# BRAKE_rev0.net
KiCad netlist of a schematic drawn in Altium Designer
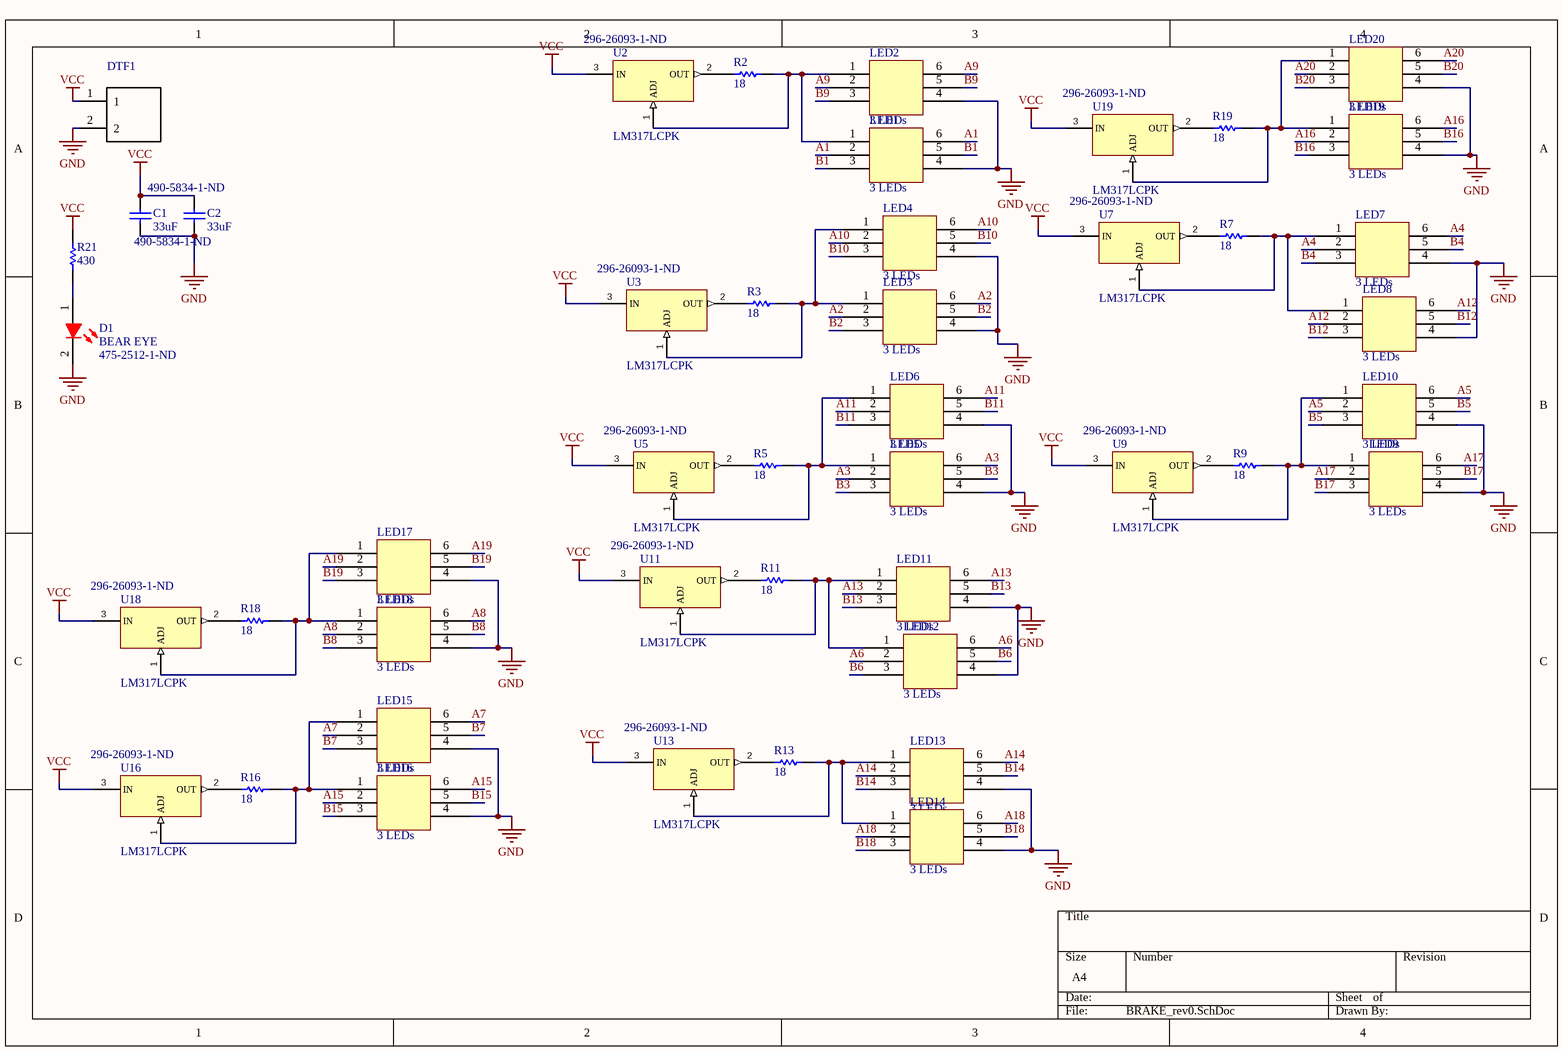
[diagram p0: BRAKE_rev0.SchDoc]

(export (version "E")
  (design (tool "Eeschema 10.0.6"))
  (components
    (comp (ref "C1")
      (value "33uF")
      (footprint "2J-Lead 6.1 x 5.3")
      (description "Capacitor (Semiconductor SIM Model)")
      (fields
        (field (name "SUPPLIER PART NUMBER 1") "490-5834-1-ND")
        (field (name "Comment") "Cap Semi")
        (field (name "PUBLISHER") "Altium Limited")
      )
      (libsource (lib "Miscellaneous Devices") (part "Cap Semi"))
    )
    (comp (ref "C2")
      (value "33uF")
      (footprint "2J-Lead 6.1 x 5.3")
      (description "Capacitor (Semiconductor SIM Model)")
      (fields
        (field (name "SUPPLIER PART NUMBER 1") "490-5834-1-ND")
        (field (name "Comment") "Cap Semi")
        (field (name "PUBLISHER") "Altium Limited")
      )
      (libsource (lib "Miscellaneous Devices") (part "Cap Semi"))
    )
    (comp (ref "D1")
      (value "BEAR EYE")
      (footprint "TOSH-0603LED_RED_V")
      (description "LED, Red 0603 (1608) 63mCd")
      (fields
        (field (name "MANUFACTURER") "Toshiba")
        (field (name "PARTNUMBER") "TLSU1008A(T04)")
        (field (name "SUPPLIER PART NUMBER 1") "475-2512-1-ND")
      )
      (libsource (lib "Altium Content Vault") (part "CMP-0444-00001-1"))
    )
    (comp (ref "DTF1")
      (value "DTF13-2P")
      (footprint "DTF13-2P")
      (description "DEUTSCH Automotive; DT RECP ASM")
      (fields (field (name "MF") "TE Connectivity") (field (name "DIGI-KEY_PART_NUMBER") "1734-1033-ND"))
      (libsource (lib "DTF13-2P") (part "DTF13-2P"))
    )
    (comp (ref "LED1")
      (value "3 LEDs")
      (footprint "3 channel led")
      (libsource (lib "PCB_BRAKE_LIGHT") (part "CLP6C-RKW-CYBA0AA3"))
    )
    (comp (ref "LED2")
      (value "3 LEDs")
      (footprint "3 channel led")
      (libsource (lib "PCB_BRAKE_LIGHT") (part "CLP6C-RKW-CYBA0AA3"))
    )
    (comp (ref "LED3")
      (value "3 LEDs")
      (footprint "3 channel led")
      (libsource (lib "PCB_BRAKE_LIGHT") (part "CLP6C-RKW-CYBA0AA3"))
    )
    (comp (ref "LED4")
      (value "3 LEDs")
      (footprint "3 channel led")
      (libsource (lib "PCB_BRAKE_LIGHT") (part "CLP6C-RKW-CYBA0AA3"))
    )
    (comp (ref "LED5")
      (value "3 LEDs")
      (footprint "3 channel led")
      (libsource (lib "PCB_BRAKE_LIGHT") (part "CLP6C-RKW-CYBA0AA3"))
    )
    (comp (ref "LED6")
      (value "3 LEDs")
      (footprint "3 channel led")
      (libsource (lib "PCB_BRAKE_LIGHT") (part "CLP6C-RKW-CYBA0AA3"))
    )
    (comp (ref "LED7")
      (value "3 LEDs")
      (footprint "3 channel led")
      (libsource (lib "PCB_BRAKE_LIGHT") (part "CLP6C-RKW-CYBA0AA3"))
    )
    (comp (ref "LED8")
      (value "3 LEDs")
      (footprint "3 channel led")
      (libsource (lib "PCB_BRAKE_LIGHT") (part "CLP6C-RKW-CYBA0AA3"))
    )
    (comp (ref "LED9")
      (value "3 LEDs")
      (footprint "3 channel led")
      (libsource (lib "PCB_BRAKE_LIGHT") (part "CLP6C-RKW-CYBA0AA3"))
    )
    (comp (ref "LED10")
      (value "3 LEDs")
      (footprint "3 channel led")
      (libsource (lib "PCB_BRAKE_LIGHT") (part "CLP6C-RKW-CYBA0AA3"))
    )
    (comp (ref "LED11")
      (value "3 LEDs")
      (footprint "3 channel led")
      (libsource (lib "PCB_BRAKE_LIGHT") (part "CLP6C-RKW-CYBA0AA3"))
    )
    (comp (ref "LED12")
      (value "3 LEDs")
      (footprint "3 channel led")
      (libsource (lib "PCB_BRAKE_LIGHT") (part "CLP6C-RKW-CYBA0AA3"))
    )
    (comp (ref "LED13")
      (value "3 LEDs")
      (footprint "3 channel led")
      (libsource (lib "PCB_BRAKE_LIGHT") (part "CLP6C-RKW-CYBA0AA3"))
    )
    (comp (ref "LED14")
      (value "3 LEDs")
      (footprint "3 channel led")
      (libsource (lib "PCB_BRAKE_LIGHT") (part "CLP6C-RKW-CYBA0AA3"))
    )
    (comp (ref "LED15")
      (value "3 LEDs")
      (footprint "3 channel led")
      (libsource (lib "PCB_BRAKE_LIGHT") (part "CLP6C-RKW-CYBA0AA3"))
    )
    (comp (ref "LED16")
      (value "3 LEDs")
      (footprint "3 channel led")
      (libsource (lib "PCB_BRAKE_LIGHT") (part "CLP6C-RKW-CYBA0AA3"))
    )
    (comp (ref "LED17")
      (value "3 LEDs")
      (footprint "3 channel led")
      (libsource (lib "PCB_BRAKE_LIGHT") (part "CLP6C-RKW-CYBA0AA3"))
    )
    (comp (ref "LED18")
      (value "3 LEDs")
      (footprint "3 channel led")
      (libsource (lib "PCB_BRAKE_LIGHT") (part "CLP6C-RKW-CYBA0AA3"))
    )
    (comp (ref "LED19")
      (value "3 LEDs")
      (footprint "3 channel led")
      (libsource (lib "PCB_BRAKE_LIGHT") (part "CLP6C-RKW-CYBA0AA3"))
    )
    (comp (ref "LED20")
      (value "3 LEDs")
      (footprint "3 channel led")
      (libsource (lib "PCB_BRAKE_LIGHT") (part "CLP6C-RKW-CYBA0AA3"))
    )
    (comp (ref "R2")
      (value "18")
      (footprint "RESC0603(1608)_L")
      (description "0603 (1608 Metric) Chip Resistor")
      (libsource (lib "Altium Content Vault") (part "RES_3"))
    )
    (comp (ref "R3")
      (value "18")
      (footprint "RESC0603(1608)_L")
      (description "0603 (1608 Metric) Chip Resistor")
      (libsource (lib "Altium Content Vault") (part "RES_3"))
    )
    (comp (ref "R5")
      (value "18")
      (footprint "RESC0603(1608)_L")
      (description "0603 (1608 Metric) Chip Resistor")
      (libsource (lib "Altium Content Vault") (part "RES_3"))
    )
    (comp (ref "R7")
      (value "18")
      (footprint "RESC0603(1608)_L")
      (description "0603 (1608 Metric) Chip Resistor")
      (libsource (lib "Altium Content Vault") (part "RES_3"))
    )
    (comp (ref "R9")
      (value "18")
      (footprint "RESC0603(1608)_L")
      (description "0603 (1608 Metric) Chip Resistor")
      (libsource (lib "Altium Content Vault") (part "RES_3"))
    )
    (comp (ref "R11")
      (value "18")
      (footprint "RESC0603(1608)_L")
      (description "0603 (1608 Metric) Chip Resistor")
      (libsource (lib "Altium Content Vault") (part "RES_3"))
    )
    (comp (ref "R13")
      (value "18")
      (footprint "RESC0603(1608)_L")
      (description "0603 (1608 Metric) Chip Resistor")
      (libsource (lib "Altium Content Vault") (part "RES_3"))
    )
    (comp (ref "R16")
      (value "18")
      (footprint "RESC0603(1608)_L")
      (description "0603 (1608 Metric) Chip Resistor")
      (libsource (lib "Altium Content Vault") (part "RES_3"))
    )
    (comp (ref "R18")
      (value "18")
      (footprint "RESC0603(1608)_L")
      (description "0603 (1608 Metric) Chip Resistor")
      (libsource (lib "Altium Content Vault") (part "RES_3"))
    )
    (comp (ref "R19")
      (value "18")
      (footprint "RESC0603(1608)_L")
      (description "0603 (1608 Metric) Chip Resistor")
      (libsource (lib "Altium Content Vault") (part "RES_3"))
    )
    (comp (ref "R21")
      (value "430")
      (footprint "RESC0603(1608)_L")
      (description "0603 (1608 Metric) Chip Resistor")
      (libsource (lib "Altium Content Vault") (part "RES_3"))
    )
    (comp (ref "U2")
      (value "LM317LCPK")
      (footprint "LM317LCPK")
      (fields (field (name "SUPPLIER PART NUMBER 1") "296-26093-1-ND"))
      (libsource (lib "BrakeLight_symbols") (part "LM317LCPK"))
    )
    (comp (ref "U3")
      (value "LM317LCPK")
      (footprint "LM317LCPK")
      (fields (field (name "SUPPLIER PART NUMBER 1") "296-26093-1-ND"))
      (libsource (lib "BrakeLight_symbols") (part "LM317LCPK"))
    )
    (comp (ref "U5")
      (value "LM317LCPK")
      (footprint "LM317LCPK")
      (fields (field (name "SUPPLIER PART NUMBER 1") "296-26093-1-ND"))
      (libsource (lib "BrakeLight_symbols") (part "LM317LCPK"))
    )
    (comp (ref "U7")
      (value "LM317LCPK")
      (footprint "LM317LCPK")
      (fields (field (name "SUPPLIER PART NUMBER 1") "296-26093-1-ND"))
      (libsource (lib "BrakeLight_symbols") (part "LM317LCPK"))
    )
    (comp (ref "U9")
      (value "LM317LCPK")
      (footprint "LM317LCPK")
      (fields (field (name "SUPPLIER PART NUMBER 1") "296-26093-1-ND"))
      (libsource (lib "BrakeLight_symbols") (part "LM317LCPK"))
    )
    (comp (ref "U11")
      (value "LM317LCPK")
      (footprint "LM317LCPK")
      (fields (field (name "SUPPLIER PART NUMBER 1") "296-26093-1-ND"))
      (libsource (lib "BrakeLight_symbols") (part "LM317LCPK"))
    )
    (comp (ref "U13")
      (value "LM317LCPK")
      (footprint "LM317LCPK")
      (fields (field (name "SUPPLIER PART NUMBER 1") "296-26093-1-ND"))
      (libsource (lib "BrakeLight_symbols") (part "LM317LCPK"))
    )
    (comp (ref "U16")
      (value "LM317LCPK")
      (footprint "LM317LCPK")
      (fields (field (name "SUPPLIER PART NUMBER 1") "296-26093-1-ND"))
      (libsource (lib "BrakeLight_symbols") (part "LM317LCPK"))
    )
    (comp (ref "U18")
      (value "LM317LCPK")
      (footprint "LM317LCPK")
      (fields (field (name "SUPPLIER PART NUMBER 1") "296-26093-1-ND"))
      (libsource (lib "BrakeLight_symbols") (part "LM317LCPK"))
    )
    (comp (ref "U19")
      (value "LM317LCPK")
      (footprint "LM317LCPK")
      (fields (field (name "SUPPLIER PART NUMBER 1") "296-26093-1-ND"))
      (libsource (lib "BrakeLight_symbols") (part "LM317LCPK"))
    )
  )
  (nets
    (net (code "1") (name "/A1") (class "Default")
      (node (ref "LED1") (pin "2") (pinfunction "2_2") (pintype "passive"))
      (node (ref "LED1") (pin "6") (pinfunction "6_6") (pintype "passive"))
    )
    (net (code "2") (name "/A2") (class "Default")
      (node (ref "LED3") (pin "2") (pinfunction "2_2") (pintype "passive"))
      (node (ref "LED3") (pin "6") (pinfunction "6_6") (pintype "passive"))
    )
    (net (code "3") (name "/A3") (class "Default")
      (node (ref "LED5") (pin "2") (pinfunction "2_2") (pintype "passive"))
      (node (ref "LED5") (pin "6") (pinfunction "6_6") (pintype "passive"))
    )
    (net (code "4") (name "/A4") (class "Default")
      (node (ref "LED7") (pin "2") (pinfunction "2_2") (pintype "passive"))
      (node (ref "LED7") (pin "6") (pinfunction "6_6") (pintype "passive"))
    )
    (net (code "5") (name "/A5") (class "Default")
      (node (ref "LED10") (pin "2") (pinfunction "2_2") (pintype "passive"))
      (node (ref "LED10") (pin "6") (pinfunction "6_6") (pintype "passive"))
    )
    (net (code "6") (name "/A6") (class "Default")
      (node (ref "LED12") (pin "2") (pinfunction "2_2") (pintype "passive"))
      (node (ref "LED12") (pin "6") (pinfunction "6_6") (pintype "passive"))
    )
    (net (code "7") (name "/A7") (class "Default")
      (node (ref "LED15") (pin "2") (pinfunction "2_2") (pintype "passive"))
      (node (ref "LED15") (pin "6") (pinfunction "6_6") (pintype "passive"))
    )
    (net (code "8") (name "/A8") (class "Default")
      (node (ref "LED18") (pin "2") (pinfunction "2_2") (pintype "passive"))
      (node (ref "LED18") (pin "6") (pinfunction "6_6") (pintype "passive"))
    )
    (net (code "9") (name "/A9") (class "Default")
      (node (ref "LED2") (pin "2") (pinfunction "2_2") (pintype "passive"))
      (node (ref "LED2") (pin "6") (pinfunction "6_6") (pintype "passive"))
    )
    (net (code "10") (name "/A10") (class "Default")
      (node (ref "LED4") (pin "2") (pinfunction "2_2") (pintype "passive"))
      (node (ref "LED4") (pin "6") (pinfunction "6_6") (pintype "passive"))
    )
    (net (code "11") (name "/A11") (class "Default")
      (node (ref "LED6") (pin "2") (pinfunction "2_2") (pintype "passive"))
      (node (ref "LED6") (pin "6") (pinfunction "6_6") (pintype "passive"))
    )
    (net (code "12") (name "/A12") (class "Default")
      (node (ref "LED8") (pin "2") (pinfunction "2_2") (pintype "passive"))
      (node (ref "LED8") (pin "6") (pinfunction "6_6") (pintype "passive"))
    )
    (net (code "13") (name "/A13") (class "Default")
      (node (ref "LED11") (pin "2") (pinfunction "2_2") (pintype "passive"))
      (node (ref "LED11") (pin "6") (pinfunction "6_6") (pintype "passive"))
    )
    (net (code "14") (name "/A14") (class "Default")
      (node (ref "LED13") (pin "2") (pinfunction "2_2") (pintype "passive"))
      (node (ref "LED13") (pin "6") (pinfunction "6_6") (pintype "passive"))
    )
    (net (code "15") (name "/A15") (class "Default")
      (node (ref "LED16") (pin "2") (pinfunction "2_2") (pintype "passive"))
      (node (ref "LED16") (pin "6") (pinfunction "6_6") (pintype "passive"))
    )
    (net (code "16") (name "/A16") (class "Default")
      (node (ref "LED19") (pin "2") (pinfunction "2_2") (pintype "passive"))
      (node (ref "LED19") (pin "6") (pinfunction "6_6") (pintype "passive"))
    )
    (net (code "17") (name "/A17") (class "Default")
      (node (ref "LED9") (pin "2") (pinfunction "2_2") (pintype "passive"))
      (node (ref "LED9") (pin "6") (pinfunction "6_6") (pintype "passive"))
    )
    (net (code "18") (name "/A18") (class "Default")
      (node (ref "LED14") (pin "2") (pinfunction "2_2") (pintype "passive"))
      (node (ref "LED14") (pin "6") (pinfunction "6_6") (pintype "passive"))
    )
    (net (code "19") (name "/A19") (class "Default")
      (node (ref "LED17") (pin "2") (pinfunction "2_2") (pintype "passive"))
      (node (ref "LED17") (pin "6") (pinfunction "6_6") (pintype "passive"))
    )
    (net (code "20") (name "/A20") (class "Default")
      (node (ref "LED20") (pin "2") (pinfunction "2_2") (pintype "passive"))
      (node (ref "LED20") (pin "6") (pinfunction "6_6") (pintype "passive"))
    )
    (net (code "21") (name "/B1") (class "Default")
      (node (ref "LED1") (pin "3") (pinfunction "3_3") (pintype "passive"))
      (node (ref "LED1") (pin "5") (pinfunction "5_5") (pintype "passive"))
    )
    (net (code "22") (name "/B2") (class "Default")
      (node (ref "LED3") (pin "3") (pinfunction "3_3") (pintype "passive"))
      (node (ref "LED3") (pin "5") (pinfunction "5_5") (pintype "passive"))
    )
    (net (code "23") (name "/B3") (class "Default")
      (node (ref "LED5") (pin "3") (pinfunction "3_3") (pintype "passive"))
      (node (ref "LED5") (pin "5") (pinfunction "5_5") (pintype "passive"))
    )
    (net (code "24") (name "/B4") (class "Default")
      (node (ref "LED7") (pin "3") (pinfunction "3_3") (pintype "passive"))
      (node (ref "LED7") (pin "5") (pinfunction "5_5") (pintype "passive"))
    )
    (net (code "25") (name "/B5") (class "Default")
      (node (ref "LED10") (pin "3") (pinfunction "3_3") (pintype "passive"))
      (node (ref "LED10") (pin "5") (pinfunction "5_5") (pintype "passive"))
    )
    (net (code "26") (name "/B6") (class "Default")
      (node (ref "LED12") (pin "3") (pinfunction "3_3") (pintype "passive"))
      (node (ref "LED12") (pin "5") (pinfunction "5_5") (pintype "passive"))
    )
    (net (code "27") (name "/B7") (class "Default")
      (node (ref "LED15") (pin "3") (pinfunction "3_3") (pintype "passive"))
      (node (ref "LED15") (pin "5") (pinfunction "5_5") (pintype "passive"))
    )
    (net (code "28") (name "/B8") (class "Default")
      (node (ref "LED18") (pin "3") (pinfunction "3_3") (pintype "passive"))
      (node (ref "LED18") (pin "5") (pinfunction "5_5") (pintype "passive"))
    )
    (net (code "29") (name "/B9") (class "Default")
      (node (ref "LED2") (pin "3") (pinfunction "3_3") (pintype "passive"))
      (node (ref "LED2") (pin "5") (pinfunction "5_5") (pintype "passive"))
    )
    (net (code "30") (name "/B10") (class "Default")
      (node (ref "LED4") (pin "3") (pinfunction "3_3") (pintype "passive"))
      (node (ref "LED4") (pin "5") (pinfunction "5_5") (pintype "passive"))
    )
    (net (code "31") (name "/B11") (class "Default")
      (node (ref "LED6") (pin "3") (pinfunction "3_3") (pintype "passive"))
      (node (ref "LED6") (pin "5") (pinfunction "5_5") (pintype "passive"))
    )
    (net (code "32") (name "/B12") (class "Default")
      (node (ref "LED8") (pin "3") (pinfunction "3_3") (pintype "passive"))
      (node (ref "LED8") (pin "5") (pinfunction "5_5") (pintype "passive"))
    )
    (net (code "33") (name "/B13") (class "Default")
      (node (ref "LED11") (pin "3") (pinfunction "3_3") (pintype "passive"))
      (node (ref "LED11") (pin "5") (pinfunction "5_5") (pintype "passive"))
    )
    (net (code "34") (name "/B14") (class "Default")
      (node (ref "LED13") (pin "3") (pinfunction "3_3") (pintype "passive"))
      (node (ref "LED13") (pin "5") (pinfunction "5_5") (pintype "passive"))
    )
    (net (code "35") (name "/B15") (class "Default")
      (node (ref "LED16") (pin "3") (pinfunction "3_3") (pintype "passive"))
      (node (ref "LED16") (pin "5") (pinfunction "5_5") (pintype "passive"))
    )
    (net (code "36") (name "/B16") (class "Default")
      (node (ref "LED19") (pin "3") (pinfunction "3_3") (pintype "passive"))
      (node (ref "LED19") (pin "5") (pinfunction "5_5") (pintype "passive"))
    )
    (net (code "37") (name "/B17") (class "Default")
      (node (ref "LED9") (pin "3") (pinfunction "3_3") (pintype "passive"))
      (node (ref "LED9") (pin "5") (pinfunction "5_5") (pintype "passive"))
    )
    (net (code "38") (name "/B18") (class "Default")
      (node (ref "LED14") (pin "3") (pinfunction "3_3") (pintype "passive"))
      (node (ref "LED14") (pin "5") (pinfunction "5_5") (pintype "passive"))
    )
    (net (code "39") (name "/B19") (class "Default")
      (node (ref "LED17") (pin "3") (pinfunction "3_3") (pintype "passive"))
      (node (ref "LED17") (pin "5") (pinfunction "5_5") (pintype "passive"))
    )
    (net (code "40") (name "/B20") (class "Default")
      (node (ref "LED20") (pin "3") (pinfunction "3_3") (pintype "passive"))
      (node (ref "LED20") (pin "5") (pinfunction "5_5") (pintype "passive"))
    )
    (net (code "41") (name "GND") (class "Default")
      (node (ref "C1") (pin "2") (pinfunction "2_2") (pintype "passive"))
      (node (ref "C2") (pin "2") (pinfunction "2_2") (pintype "passive"))
      (node (ref "D1") (pin "2") (pinfunction "K_2") (pintype "passive"))
      (node (ref "DTF1") (pin "2") (pinfunction "2_2") (pintype "passive"))
      (node (ref "LED1") (pin "4") (pinfunction "4_4") (pintype "passive"))
      (node (ref "LED10") (pin "4") (pinfunction "4_4") (pintype "passive"))
      (node (ref "LED11") (pin "4") (pinfunction "4_4") (pintype "passive"))
      (node (ref "LED12") (pin "4") (pinfunction "4_4") (pintype "passive"))
      (node (ref "LED13") (pin "4") (pinfunction "4_4") (pintype "passive"))
      (node (ref "LED14") (pin "4") (pinfunction "4_4") (pintype "passive"))
      (node (ref "LED15") (pin "4") (pinfunction "4_4") (pintype "passive"))
      (node (ref "LED16") (pin "4") (pinfunction "4_4") (pintype "passive"))
      (node (ref "LED17") (pin "4") (pinfunction "4_4") (pintype "passive"))
      (node (ref "LED18") (pin "4") (pinfunction "4_4") (pintype "passive"))
      (node (ref "LED19") (pin "4") (pinfunction "4_4") (pintype "passive"))
      (node (ref "LED2") (pin "4") (pinfunction "4_4") (pintype "passive"))
      (node (ref "LED20") (pin "4") (pinfunction "4_4") (pintype "passive"))
      (node (ref "LED3") (pin "4") (pinfunction "4_4") (pintype "passive"))
      (node (ref "LED4") (pin "4") (pinfunction "4_4") (pintype "passive"))
      (node (ref "LED5") (pin "4") (pinfunction "4_4") (pintype "passive"))
      (node (ref "LED6") (pin "4") (pinfunction "4_4") (pintype "passive"))
      (node (ref "LED7") (pin "4") (pinfunction "4_4") (pintype "passive"))
      (node (ref "LED8") (pin "4") (pinfunction "4_4") (pintype "passive"))
      (node (ref "LED9") (pin "4") (pinfunction "4_4") (pintype "passive"))
    )
    (net (code "42") (name "Net-(D1-A)") (class "Default")
      (node (ref "D1") (pin "1") (pinfunction "A_1") (pintype "passive"))
      (node (ref "R21") (pin "1") (pinfunction "1_1") (pintype "passive"))
    )
    (net (code "43") (name "Net-(U2-ADJ)") (class "Default")
      (node (ref "LED1") (pin "1") (pinfunction "1_1") (pintype "passive"))
      (node (ref "LED2") (pin "1") (pinfunction "1_1") (pintype "passive"))
      (node (ref "R2") (pin "1") (pinfunction "1_1") (pintype "passive"))
      (node (ref "U2") (pin "1") (pinfunction "ADJ_1") (pintype "input"))
    )
    (net (code "44") (name "Net-(U2-OUT)") (class "Default")
      (node (ref "R2") (pin "2") (pinfunction "2_2") (pintype "passive"))
      (node (ref "U2") (pin "2") (pinfunction "OUT_2") (pintype "output"))
    )
    (net (code "45") (name "Net-(U3-ADJ)") (class "Default")
      (node (ref "LED3") (pin "1") (pinfunction "1_1") (pintype "passive"))
      (node (ref "LED4") (pin "1") (pinfunction "1_1") (pintype "passive"))
      (node (ref "R3") (pin "1") (pinfunction "1_1") (pintype "passive"))
      (node (ref "U3") (pin "1") (pinfunction "ADJ_1") (pintype "input"))
    )
    (net (code "46") (name "Net-(U3-OUT)") (class "Default")
      (node (ref "R3") (pin "2") (pinfunction "2_2") (pintype "passive"))
      (node (ref "U3") (pin "2") (pinfunction "OUT_2") (pintype "output"))
    )
    (net (code "47") (name "Net-(U5-ADJ)") (class "Default")
      (node (ref "LED5") (pin "1") (pinfunction "1_1") (pintype "passive"))
      (node (ref "LED6") (pin "1") (pinfunction "1_1") (pintype "passive"))
      (node (ref "R5") (pin "1") (pinfunction "1_1") (pintype "passive"))
      (node (ref "U5") (pin "1") (pinfunction "ADJ_1") (pintype "input"))
    )
    (net (code "48") (name "Net-(U5-OUT)") (class "Default")
      (node (ref "R5") (pin "2") (pinfunction "2_2") (pintype "passive"))
      (node (ref "U5") (pin "2") (pinfunction "OUT_2") (pintype "output"))
    )
    (net (code "49") (name "Net-(U7-ADJ)") (class "Default")
      (node (ref "LED7") (pin "1") (pinfunction "1_1") (pintype "passive"))
      (node (ref "LED8") (pin "1") (pinfunction "1_1") (pintype "passive"))
      (node (ref "R7") (pin "1") (pinfunction "1_1") (pintype "passive"))
      (node (ref "U7") (pin "1") (pinfunction "ADJ_1") (pintype "input"))
    )
    (net (code "50") (name "Net-(U7-OUT)") (class "Default")
      (node (ref "R7") (pin "2") (pinfunction "2_2") (pintype "passive"))
      (node (ref "U7") (pin "2") (pinfunction "OUT_2") (pintype "output"))
    )
    (net (code "51") (name "Net-(U9-ADJ)") (class "Default")
      (node (ref "LED10") (pin "1") (pinfunction "1_1") (pintype "passive"))
      (node (ref "LED9") (pin "1") (pinfunction "1_1") (pintype "passive"))
      (node (ref "R9") (pin "1") (pinfunction "1_1") (pintype "passive"))
      (node (ref "U9") (pin "1") (pinfunction "ADJ_1") (pintype "input"))
    )
    (net (code "52") (name "Net-(U9-OUT)") (class "Default")
      (node (ref "R9") (pin "2") (pinfunction "2_2") (pintype "passive"))
      (node (ref "U9") (pin "2") (pinfunction "OUT_2") (pintype "output"))
    )
    (net (code "53") (name "Net-(U11-ADJ)") (class "Default")
      (node (ref "LED11") (pin "1") (pinfunction "1_1") (pintype "passive"))
      (node (ref "LED12") (pin "1") (pinfunction "1_1") (pintype "passive"))
      (node (ref "R11") (pin "1") (pinfunction "1_1") (pintype "passive"))
      (node (ref "U11") (pin "1") (pinfunction "ADJ_1") (pintype "input"))
    )
    (net (code "54") (name "Net-(U11-OUT)") (class "Default")
      (node (ref "R11") (pin "2") (pinfunction "2_2") (pintype "passive"))
      (node (ref "U11") (pin "2") (pinfunction "OUT_2") (pintype "output"))
    )
    (net (code "55") (name "Net-(U13-ADJ)") (class "Default")
      (node (ref "LED13") (pin "1") (pinfunction "1_1") (pintype "passive"))
      (node (ref "LED14") (pin "1") (pinfunction "1_1") (pintype "passive"))
      (node (ref "R13") (pin "1") (pinfunction "1_1") (pintype "passive"))
      (node (ref "U13") (pin "1") (pinfunction "ADJ_1") (pintype "input"))
    )
    (net (code "56") (name "Net-(U13-OUT)") (class "Default")
      (node (ref "R13") (pin "2") (pinfunction "2_2") (pintype "passive"))
      (node (ref "U13") (pin "2") (pinfunction "OUT_2") (pintype "output"))
    )
    (net (code "57") (name "Net-(U16-ADJ)") (class "Default")
      (node (ref "LED15") (pin "1") (pinfunction "1_1") (pintype "passive"))
      (node (ref "LED16") (pin "1") (pinfunction "1_1") (pintype "passive"))
      (node (ref "R16") (pin "1") (pinfunction "1_1") (pintype "passive"))
      (node (ref "U16") (pin "1") (pinfunction "ADJ_1") (pintype "input"))
    )
    (net (code "58") (name "Net-(U16-OUT)") (class "Default")
      (node (ref "R16") (pin "2") (pinfunction "2_2") (pintype "passive"))
      (node (ref "U16") (pin "2") (pinfunction "OUT_2") (pintype "output"))
    )
    (net (code "59") (name "Net-(U18-ADJ)") (class "Default")
      (node (ref "LED17") (pin "1") (pinfunction "1_1") (pintype "passive"))
      (node (ref "LED18") (pin "1") (pinfunction "1_1") (pintype "passive"))
      (node (ref "R18") (pin "1") (pinfunction "1_1") (pintype "passive"))
      (node (ref "U18") (pin "1") (pinfunction "ADJ_1") (pintype "input"))
    )
    (net (code "60") (name "Net-(U18-OUT)") (class "Default")
      (node (ref "R18") (pin "2") (pinfunction "2_2") (pintype "passive"))
      (node (ref "U18") (pin "2") (pinfunction "OUT_2") (pintype "output"))
    )
    (net (code "61") (name "Net-(U19-ADJ)") (class "Default")
      (node (ref "LED19") (pin "1") (pinfunction "1_1") (pintype "passive"))
      (node (ref "LED20") (pin "1") (pinfunction "1_1") (pintype "passive"))
      (node (ref "R19") (pin "1") (pinfunction "1_1") (pintype "passive"))
      (node (ref "U19") (pin "1") (pinfunction "ADJ_1") (pintype "input"))
    )
    (net (code "62") (name "Net-(U19-OUT)") (class "Default")
      (node (ref "R19") (pin "2") (pinfunction "2_2") (pintype "passive"))
      (node (ref "U19") (pin "2") (pinfunction "OUT_2") (pintype "output"))
    )
    (net (code "63") (name "VCC") (class "Default")
      (node (ref "C1") (pin "1") (pinfunction "1_1") (pintype "passive"))
      (node (ref "C2") (pin "1") (pinfunction "1_1") (pintype "passive"))
      (node (ref "DTF1") (pin "1") (pinfunction "1_1") (pintype "passive"))
      (node (ref "R21") (pin "2") (pinfunction "2_2") (pintype "passive"))
      (node (ref "U11") (pin "3") (pinfunction "IN_3") (pintype "passive"))
      (node (ref "U13") (pin "3") (pinfunction "IN_3") (pintype "passive"))
      (node (ref "U16") (pin "3") (pinfunction "IN_3") (pintype "passive"))
      (node (ref "U18") (pin "3") (pinfunction "IN_3") (pintype "passive"))
      (node (ref "U19") (pin "3") (pinfunction "IN_3") (pintype "passive"))
      (node (ref "U2") (pin "3") (pinfunction "IN_3") (pintype "passive"))
      (node (ref "U3") (pin "3") (pinfunction "IN_3") (pintype "passive"))
      (node (ref "U5") (pin "3") (pinfunction "IN_3") (pintype "passive"))
      (node (ref "U7") (pin "3") (pinfunction "IN_3") (pintype "passive"))
      (node (ref "U9") (pin "3") (pinfunction "IN_3") (pintype "passive"))
    )
  )
)
